# 1S_2S.net
KiCad netlist of a schematic drawn in Altium Designer
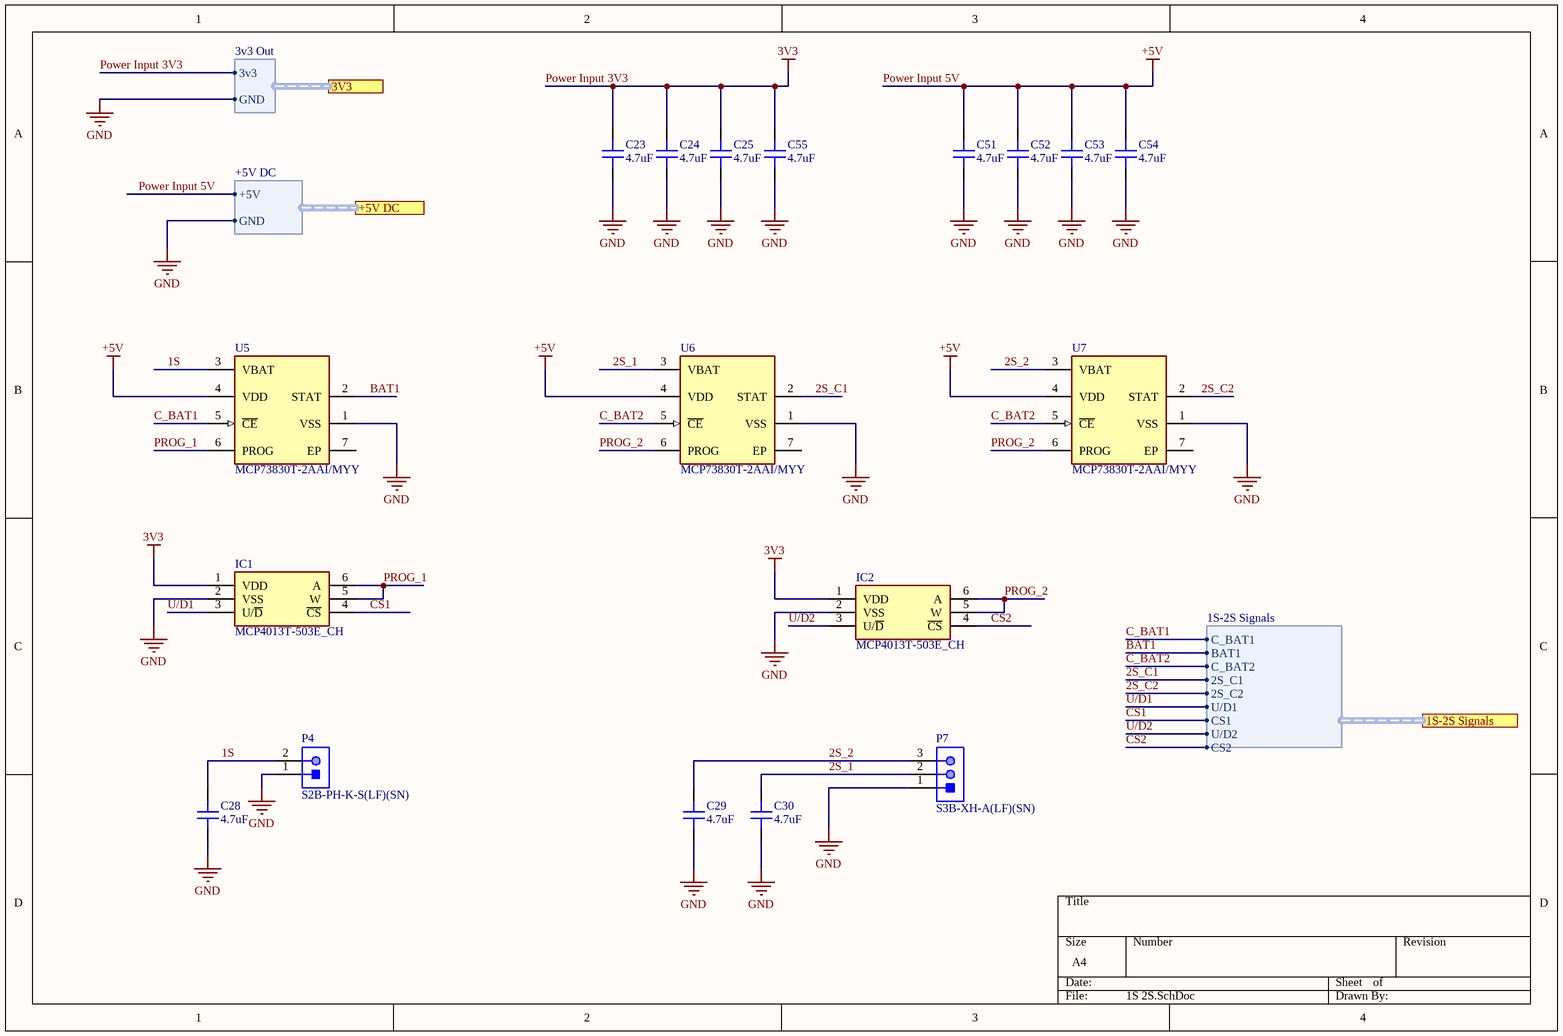
[diagram p0: 1S 2S.SchDoc]

(export (version "E")
  (design (tool "Eeschema 10.0.6"))
  (components
    (comp (ref "C23")
      (value "4.7uF")
      (footprint "CAP 0603_1608")
      (description "CAP CER 100PF 50V C0G/NP0 0603")
      (fields (field (name "PART NUMBER") "C0603X101F5GACAUTO") (field (name "MANUFACTURER") "KEMET"))
      (libsource (lib "Celestial Altium Library - altium_library (2)") (part "Capacitor"))
    )
    (comp (ref "C24")
      (value "4.7uF")
      (footprint "CAP 0603_1608")
      (description "CAP CER 100PF 50V C0G/NP0 0603")
      (fields (field (name "PART NUMBER") "C0603X101F5GACAUTO") (field (name "MANUFACTURER") "KEMET"))
      (libsource (lib "Celestial Altium Library - altium_library (2)") (part "Capacitor"))
    )
    (comp (ref "C25")
      (value "4.7uF")
      (footprint "CAP 0603_1608")
      (description "CAP CER 100PF 50V C0G/NP0 0603")
      (fields (field (name "PART NUMBER") "C0603X101F5GACAUTO") (field (name "MANUFACTURER") "KEMET"))
      (libsource (lib "Celestial Altium Library - altium_library (2)") (part "Capacitor"))
    )
    (comp (ref "C28")
      (value "4.7uF")
      (footprint "CAP 0603_1608")
      (description "CAP CER 100PF 50V C0G/NP0 0603")
      (fields (field (name "PART NUMBER") "C0603X101F5GACAUTO") (field (name "MANUFACTURER") "KEMET"))
      (libsource (lib "Celestial Altium Library - altium_library (2)") (part "Capacitor"))
    )
    (comp (ref "C29")
      (value "4.7uF")
      (footprint "CAP 0603_1608")
      (description "CAP CER 100PF 50V C0G/NP0 0603")
      (fields (field (name "PART NUMBER") "C0603X101F5GACAUTO") (field (name "MANUFACTURER") "KEMET"))
      (libsource (lib "Celestial Altium Library - altium_library (2)") (part "Capacitor"))
    )
    (comp (ref "C30")
      (value "4.7uF")
      (footprint "CAP 0603_1608")
      (description "CAP CER 100PF 50V C0G/NP0 0603")
      (fields (field (name "PART NUMBER") "C0603X101F5GACAUTO") (field (name "MANUFACTURER") "KEMET"))
      (libsource (lib "Celestial Altium Library - altium_library (2)") (part "Capacitor"))
    )
    (comp (ref "C51")
      (value "4.7uF")
      (footprint "CAP 0603_1608")
      (description "CAP CER 100PF 50V C0G/NP0 0603")
      (fields (field (name "PART NUMBER") "C0603X101F5GACAUTO") (field (name "MANUFACTURER") "KEMET"))
      (libsource (lib "Celestial Altium Library - altium_library (2)") (part "Capacitor"))
    )
    (comp (ref "C52")
      (value "4.7uF")
      (footprint "CAP 0603_1608")
      (description "CAP CER 100PF 50V C0G/NP0 0603")
      (fields (field (name "PART NUMBER") "C0603X101F5GACAUTO") (field (name "MANUFACTURER") "KEMET"))
      (libsource (lib "Celestial Altium Library - altium_library (2)") (part "Capacitor"))
    )
    (comp (ref "C53")
      (value "4.7uF")
      (footprint "CAP 0603_1608")
      (description "CAP CER 100PF 50V C0G/NP0 0603")
      (fields (field (name "PART NUMBER") "C0603X101F5GACAUTO") (field (name "MANUFACTURER") "KEMET"))
      (libsource (lib "Celestial Altium Library - altium_library (2)") (part "Capacitor"))
    )
    (comp (ref "C54")
      (value "4.7uF")
      (footprint "CAP 0603_1608")
      (description "CAP CER 100PF 50V C0G/NP0 0603")
      (fields (field (name "PART NUMBER") "C0603X101F5GACAUTO") (field (name "MANUFACTURER") "KEMET"))
      (libsource (lib "Celestial Altium Library - altium_library (2)") (part "Capacitor"))
    )
    (comp (ref "C55")
      (value "4.7uF")
      (footprint "CAP 0603_1608")
      (description "CAP CER 100PF 50V C0G/NP0 0603")
      (fields (field (name "PART NUMBER") "C0603X101F5GACAUTO") (field (name "MANUFACTURER") "KEMET"))
      (libsource (lib "Celestial Altium Library - altium_library (2)") (part "Capacitor"))
    )
    (comp (ref "IC1")
      (value "MCP4013T-503E_CH")
      (footprint "SamacSys:SOT95P280X145-6N")
      (description "Integrated Circuit")
      (fields
        (field (name "MANUFACTURER_PART_NUMBER") "MCP4013T-503E/CH")
        (field (name "MOUSER PART NUMBER") "579-MCP4013T-503E/CH")
      )
      (libsource (lib "*") (part "MCP4013T-503E_CH"))
    )
    (comp (ref "IC2")
      (value "MCP4013T-503E_CH")
      (footprint "SamacSys:SOT95P280X145-6N")
      (description "Integrated Circuit")
      (fields
        (field (name "MANUFACTURER_PART_NUMBER") "MCP4013T-503E/CH")
        (field (name "MOUSER PART NUMBER") "579-MCP4013T-503E/CH")
      )
      (libsource (lib "*") (part "MCP4013T-503E_CH"))
    )
    (comp (ref "P4")
      (value "S2B-PH-K-S(LF)(SN)")
      (footprint "JST-S2B-PH-K-S_V")
      (fields (field (name "TOLERANCE") "20%"))
      (libsource (lib "Altium Content Vault") (part "CN-1P-M-R2"))
    )
    (comp (ref "P7")
      (value "S3B-XH-A(LF)(SN)")
      (footprint "JST-S3B-XH-A(LF)(SN)_V")
      (libsource (lib "Altium Content Vault") (part "CN-1P-M-R3"))
    )
    (comp (ref "U5")
      (value "MCP73830T-2AAI/MYY")
      (footprint "FP-C04-078-IPC_B")
      (description "IC BATT MGMT LI-ION 1A 6TDFN")
      (fields
        (field (name "OCTOPART") "https://octopart.com/mcp73830t-2aai%2Fmyy-microchip-20908428")
        (field (name "MANUFACTURER") "Microchip")
      )
      (libsource (lib "Altium Content Vault") (part "6fc9ee82f4b017295cdc0d3a0aeffec"))
    )
    (comp (ref "U6")
      (value "MCP73830T-2AAI/MYY")
      (footprint "FP-C04-078-IPC_B")
      (description "IC BATT MGMT LI-ION 1A 6TDFN")
      (fields
        (field (name "OCTOPART") "https://octopart.com/mcp73830t-2aai%2Fmyy-microchip-20908428")
        (field (name "MANUFACTURER") "Microchip")
      )
      (libsource (lib "Altium Content Vault") (part "6fc9ee82f4b017295cdc0d3a0aeffec"))
    )
    (comp (ref "U7")
      (value "MCP73830T-2AAI/MYY")
      (footprint "FP-C04-078-IPC_B")
      (description "IC BATT MGMT LI-ION 1A 6TDFN")
      (fields
        (field (name "OCTOPART") "https://octopart.com/mcp73830t-2aai%2Fmyy-microchip-20908428")
        (field (name "MANUFACTURER") "Microchip")
      )
      (libsource (lib "Altium Content Vault") (part "6fc9ee82f4b017295cdc0d3a0aeffec"))
    )
  )
  (nets
    (net (code "6") (name "+5V") (class "Default")
      (node (ref "C51") (pin "2") (pinfunction "2_2") (pintype "passive"))
      (node (ref "C52") (pin "2") (pinfunction "2_2") (pintype "passive"))
      (node (ref "C53") (pin "2") (pinfunction "2_2") (pintype "passive"))
      (node (ref "C54") (pin "2") (pinfunction "2_2") (pintype "passive"))
      (node (ref "U5") (pin "4") (pinfunction "VDD_4") (pintype "power_in"))
      (node (ref "U6") (pin "4") (pinfunction "VDD_4") (pintype "power_in"))
      (node (ref "U7") (pin "4") (pinfunction "VDD_4") (pintype "power_in"))
    )
    (net (code "7") (name "/1S") (class "Default")
      (node (ref "C28") (pin "2") (pinfunction "2_2") (pintype "passive"))
      (node (ref "P4") (pin "2") (pinfunction "2_2") (pintype "passive"))
      (node (ref "U5") (pin "3") (pinfunction "VBAT_3") (pintype "power_in"))
    )
    (net (code "8") (name "/2S_1") (class "Default")
      (node (ref "C30") (pin "2") (pinfunction "2_2") (pintype "passive"))
      (node (ref "P7") (pin "2") (pinfunction "2_2") (pintype "passive"))
      (node (ref "U6") (pin "3") (pinfunction "VBAT_3") (pintype "power_in"))
    )
    (net (code "9") (name "/2S_2") (class "Default")
      (node (ref "C29") (pin "2") (pinfunction "2_2") (pintype "passive"))
      (node (ref "P7") (pin "3") (pinfunction "3_3") (pintype "passive"))
      (node (ref "U7") (pin "3") (pinfunction "VBAT_3") (pintype "power_in"))
    )
    (net (code "10") (name "/2S_C1") (class "Default")
      (node (ref "U6") (pin "2") (pinfunction "STAT_2") (pintype "open_collector"))
    )
    (net (code "11") (name "/2S_C2") (class "Default")
      (node (ref "U7") (pin "2") (pinfunction "STAT_2") (pintype "open_collector"))
    )
    (net (code "12") (name "/BAT1") (class "Default")
      (node (ref "U5") (pin "2") (pinfunction "STAT_2") (pintype "open_collector"))
    )
    (net (code "13") (name "/CS1") (class "Default")
      (node (ref "IC1") (pin "4") (pinfunction "~{CS}_4") (pintype "passive"))
    )
    (net (code "14") (name "/CS2") (class "Default")
      (node (ref "IC2") (pin "4") (pinfunction "~{CS}_4") (pintype "passive"))
    )
    (net (code "15") (name "/C_BAT1") (class "Default")
      (node (ref "U5") (pin "5") (pinfunction "~{CE}_5") (pintype "input"))
    )
    (net (code "16") (name "/C_BAT2") (class "Default")
      (node (ref "U6") (pin "5") (pinfunction "~{CE}_5") (pintype "input"))
      (node (ref "U7") (pin "5") (pinfunction "~{CE}_5") (pintype "input"))
    )
    (net (code "17") (name "/PROG_1") (class "Default")
      (node (ref "IC1") (pin "5") (pinfunction "W_5") (pintype "passive"))
      (node (ref "IC1") (pin "6") (pinfunction "A_6") (pintype "passive"))
      (node (ref "U5") (pin "6") (pinfunction "PROG_6") (pintype "passive"))
    )
    (net (code "18") (name "/PROG_2") (class "Default")
      (node (ref "IC2") (pin "5") (pinfunction "W_5") (pintype "passive"))
      (node (ref "IC2") (pin "6") (pinfunction "A_6") (pintype "passive"))
      (node (ref "U6") (pin "6") (pinfunction "PROG_6") (pintype "passive"))
      (node (ref "U7") (pin "6") (pinfunction "PROG_6") (pintype "passive"))
    )
    (net (code "19") (name "/U{slash}D1") (class "Default")
      (node (ref "IC1") (pin "3") (pinfunction "U/~{D}_3") (pintype "passive"))
    )
    (net (code "20") (name "/U{slash}D2") (class "Default")
      (node (ref "IC2") (pin "3") (pinfunction "U/~{D}_3") (pintype "passive"))
    )
    (net (code "24") (name "3V3") (class "Default")
      (node (ref "C23") (pin "2") (pinfunction "2_2") (pintype "passive"))
      (node (ref "C24") (pin "2") (pinfunction "2_2") (pintype "passive"))
      (node (ref "C25") (pin "2") (pinfunction "2_2") (pintype "passive"))
      (node (ref "C55") (pin "2") (pinfunction "2_2") (pintype "passive"))
      (node (ref "IC1") (pin "1") (pinfunction "VDD_1") (pintype "passive"))
      (node (ref "IC2") (pin "1") (pinfunction "VDD_1") (pintype "passive"))
    )
    (net (code "25") (name "GND") (class "Default")
      (node (ref "C23") (pin "1") (pinfunction "1_1") (pintype "passive"))
      (node (ref "C24") (pin "1") (pinfunction "1_1") (pintype "passive"))
      (node (ref "C25") (pin "1") (pinfunction "1_1") (pintype "passive"))
      (node (ref "C28") (pin "1") (pinfunction "1_1") (pintype "passive"))
      (node (ref "C29") (pin "1") (pinfunction "1_1") (pintype "passive"))
      (node (ref "C30") (pin "1") (pinfunction "1_1") (pintype "passive"))
      (node (ref "C51") (pin "1") (pinfunction "1_1") (pintype "passive"))
      (node (ref "C52") (pin "1") (pinfunction "1_1") (pintype "passive"))
      (node (ref "C53") (pin "1") (pinfunction "1_1") (pintype "passive"))
      (node (ref "C54") (pin "1") (pinfunction "1_1") (pintype "passive"))
      (node (ref "C55") (pin "1") (pinfunction "1_1") (pintype "passive"))
      (node (ref "IC1") (pin "2") (pinfunction "VSS_2") (pintype "passive"))
      (node (ref "IC2") (pin "2") (pinfunction "VSS_2") (pintype "passive"))
      (node (ref "P4") (pin "1") (pinfunction "1_1") (pintype "passive"))
      (node (ref "P7") (pin "1") (pinfunction "1_1") (pintype "passive"))
      (node (ref "U5") (pin "1") (pinfunction "VSS_1") (pintype "power_in"))
      (node (ref "U6") (pin "1") (pinfunction "VSS_1") (pintype "power_in"))
      (node (ref "U7") (pin "1") (pinfunction "VSS_1") (pintype "power_in"))
    )
    (net (code "26") (name "unconnected-(U5-EP-Pad7)") (class "Default")
      (node (ref "U5") (pin "7") (pinfunction "EP_7") (pintype "power_in"))
    )
    (net (code "27") (name "unconnected-(U6-EP-Pad7)") (class "Default")
      (node (ref "U6") (pin "7") (pinfunction "EP_7") (pintype "power_in"))
    )
    (net (code "28") (name "unconnected-(U7-EP-Pad7)") (class "Default")
      (node (ref "U7") (pin "7") (pinfunction "EP_7") (pintype "power_in"))
    )
  )
)
